# 02.net
KiCad netlist of a schematic drawn in Altium Designer
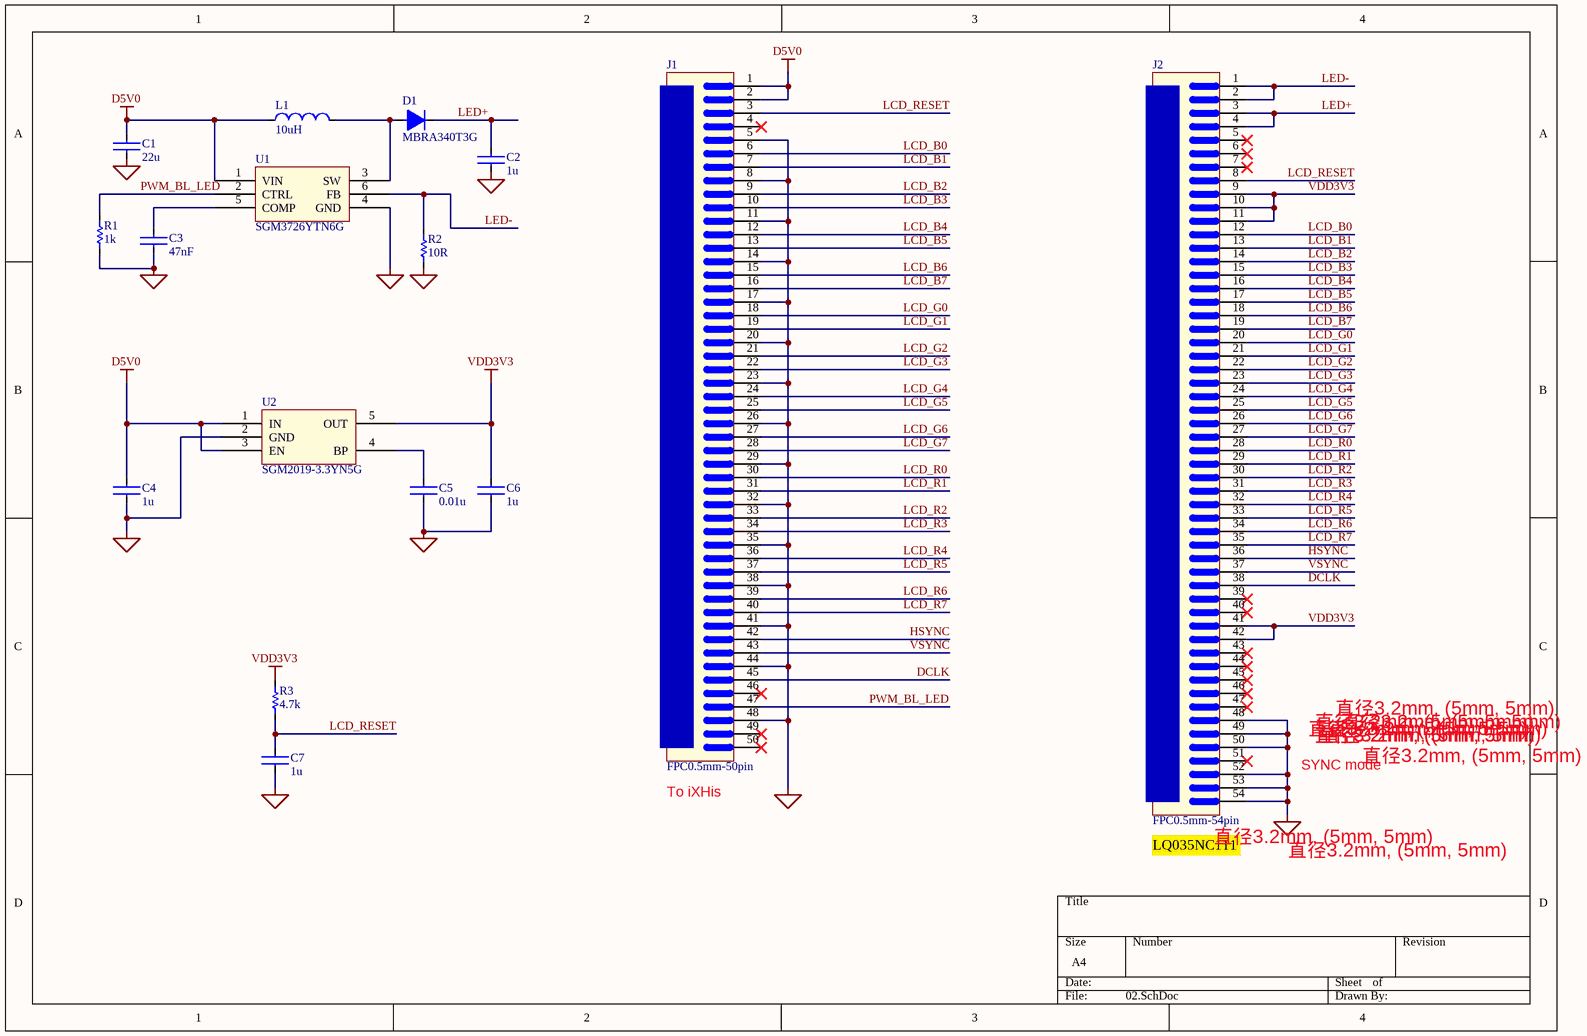
[diagram p0: 02.SchDoc]

(export (version "E")
  (design (tool "Eeschema 10.0.6"))
  (components
    (comp (ref "C1")
      (value "22u")
      (footprint "CAPC1608X09N_C0603")
      (description "CAP,Ceramic,X7R,10%,6.3V,22uF,0603")
      (libsource (lib "C0603") (part "CAP114"))
    )
    (comp (ref "C2")
      (value "1u")
      (footprint "CAPC2012X14N_C0805")
      (description "CAP,Ceramic,X7R,10%,25V,1uF,0805")
      (libsource (lib "C0805") (part "CAP110"))
    )
    (comp (ref "C3")
      (value "47nF")
      (footprint "CAPC1608X09N_C0603")
      (description "CAP,Ceramic,X7R,10%,50V,47nF,0603")
      (libsource (lib "C0603") (part "CAP115"))
    )
    (comp (ref "C4")
      (value "1u")
      (footprint "CAPC1608X09N_C0603")
      (description "CAP,Ceramic,X7R,10%,16V,1uF,0603")
      (libsource (lib "C0603") (part "CAP12"))
    )
    (comp (ref "C5")
      (value "0.01u")
      (footprint "CAPC1608X09N_C0603")
      (description "CAP,Ceramic,X7R,10%,50V,0.01uF,0603")
      (libsource (lib "C0603") (part "CAP112"))
    )
    (comp (ref "C6")
      (value "1u")
      (footprint "CAPC1608X09N_C0603")
      (description "CAP,Ceramic,X7R,10%,16V,1uF,0603")
      (libsource (lib "AD15_libpkg") (part "CAP12"))
    )
    (comp (ref "C7")
      (value "1u")
      (footprint "CAPC1608X09N_C0603")
      (description "CAP,Ceramic,X7R,10%,16V,1uF,0603")
      (libsource (lib "C0603") (part "CAP12"))
    )
    (comp (ref "D1")
      (value "MBRA340T3G")
      (footprint "DIOM4326X23N_SMA")
      (description "Schottky Barrier Rectifier,40V,3A,SMA")
      (libsource (lib "AD15_schlib") (part "MBRA340T3G"))
    )
    (comp (ref "J1")
      (value "FPC0.5mm-50pin")
      (footprint "FPC0.5mm-50pin")
      (description "FFC socket,50-Pin,top contact,0.5mm Pitch,SMD")
      (libsource (lib "AD15_schlib") (part "FPC0.5mm_04"))
    )
    (comp (ref "J2")
      (value "FPC0.5mm-54pin")
      (footprint "FPC0.5mm-54pin")
      (description "FFC socket,54-Pin,bottom contact,0.5mm Pitch,SMD")
      (libsource (lib "AD15_schlib") (part "FPC0.5mm_03"))
    )
    (comp (ref "L1")
      (value "10uH")
      (footprint "NRS3015T100MNGH")
      (description "Inductor,10uH,700mA,0.22ohm,SMD")
      (libsource (lib "AD15_schlib") (part "NRS3015T100MNGH"))
    )
    (comp (ref "R1")
      (value "1k")
      (footprint "RESC1608X05N_R0603")
      (description "RES,1k,1%,1/10W,0603")
      (libsource (lib "R0603") (part "RES11"))
    )
    (comp (ref "R2")
      (value "10R")
      (footprint "R0805")
      (description "RES,10R,1%,1/8W,0805")
      (libsource (lib "AD15_schlib") (part "RES113_2"))
    )
    (comp (ref "R3")
      (value "4.7k")
      (footprint "RESC1608X05N_R0603")
      (description "RES,4.7k,1%,1/10W,0603")
      (libsource (lib "R0603") (part "RES15"))
    )
    (comp (ref "U1")
      (value "SGM3726YTN6G")
      (footprint "TSOT23-6_SGM3726")
      (description "IC, boost converter, 1.1A, TSOT23-6")
      (libsource (lib "AD15_SGM_schlib") (part "SGM3726YTN6G"))
    )
    (comp (ref "U2")
      (value "SGM2019-3.3YN5G")
      (footprint "SOT95P280X125-5N_SGM2019")
      (description "IC,LDO 3.3V@300mA,SOT23-5")
      (libsource (lib "AD15_SGM_schlib") (part "SGM2019-3.3"))
    )
  )
  (nets
    (net (code "1") (name "/DCLK") (class "Default")
      (node (ref "J1") (pin "45") (pinfunction "45_45") (pintype "passive"))
      (node (ref "J2") (pin "38") (pinfunction "38_38") (pintype "passive"))
    )
    (net (code "2") (name "/HSYNC") (class "Default")
      (node (ref "J1") (pin "42") (pinfunction "42_42") (pintype "passive"))
      (node (ref "J2") (pin "36") (pinfunction "36_36") (pintype "passive"))
    )
    (net (code "3") (name "/LCD_B0") (class "Default")
      (node (ref "J1") (pin "6") (pinfunction "5_6") (pintype "passive"))
      (node (ref "J2") (pin "12") (pinfunction "12_12") (pintype "passive"))
    )
    (net (code "4") (name "/LCD_B1") (class "Default")
      (node (ref "J1") (pin "7") (pinfunction "6_7") (pintype "passive"))
      (node (ref "J2") (pin "13") (pinfunction "13_13") (pintype "passive"))
    )
    (net (code "5") (name "/LCD_B2") (class "Default")
      (node (ref "J1") (pin "9") (pinfunction "8_9") (pintype "passive"))
      (node (ref "J2") (pin "14") (pinfunction "14_14") (pintype "passive"))
    )
    (net (code "6") (name "/LCD_B3") (class "Default")
      (node (ref "J1") (pin "10") (pinfunction "9_10") (pintype "passive"))
      (node (ref "J2") (pin "15") (pinfunction "15_15") (pintype "passive"))
    )
    (net (code "7") (name "/LCD_B4") (class "Default")
      (node (ref "J1") (pin "12") (pinfunction "12_12") (pintype "passive"))
      (node (ref "J2") (pin "16") (pinfunction "16_16") (pintype "passive"))
    )
    (net (code "8") (name "/LCD_B5") (class "Default")
      (node (ref "J1") (pin "13") (pinfunction "13_13") (pintype "passive"))
      (node (ref "J2") (pin "17") (pinfunction "17_17") (pintype "passive"))
    )
    (net (code "9") (name "/LCD_B6") (class "Default")
      (node (ref "J1") (pin "15") (pinfunction "15_15") (pintype "passive"))
      (node (ref "J2") (pin "18") (pinfunction "18_18") (pintype "passive"))
    )
    (net (code "10") (name "/LCD_B7") (class "Default")
      (node (ref "J1") (pin "16") (pinfunction "16_16") (pintype "passive"))
      (node (ref "J2") (pin "19") (pinfunction "19_19") (pintype "passive"))
    )
    (net (code "11") (name "/LCD_G0") (class "Default")
      (node (ref "J1") (pin "18") (pinfunction "18_18") (pintype "passive"))
      (node (ref "J2") (pin "20") (pinfunction "20_20") (pintype "passive"))
    )
    (net (code "12") (name "/LCD_G1") (class "Default")
      (node (ref "J1") (pin "19") (pinfunction "19_19") (pintype "passive"))
      (node (ref "J2") (pin "21") (pinfunction "21_21") (pintype "passive"))
    )
    (net (code "13") (name "/LCD_G2") (class "Default")
      (node (ref "J1") (pin "21") (pinfunction "21_21") (pintype "passive"))
      (node (ref "J2") (pin "22") (pinfunction "22_22") (pintype "passive"))
    )
    (net (code "14") (name "/LCD_G3") (class "Default")
      (node (ref "J1") (pin "22") (pinfunction "22_22") (pintype "passive"))
      (node (ref "J2") (pin "23") (pinfunction "23_23") (pintype "passive"))
    )
    (net (code "15") (name "/LCD_G4") (class "Default")
      (node (ref "J1") (pin "24") (pinfunction "24_24") (pintype "passive"))
      (node (ref "J2") (pin "24") (pinfunction "24_24") (pintype "passive"))
    )
    (net (code "16") (name "/LCD_G5") (class "Default")
      (node (ref "J1") (pin "25") (pinfunction "25_25") (pintype "passive"))
      (node (ref "J2") (pin "25") (pinfunction "25_25") (pintype "passive"))
    )
    (net (code "17") (name "/LCD_G6") (class "Default")
      (node (ref "J1") (pin "27") (pinfunction "27_27") (pintype "passive"))
      (node (ref "J2") (pin "26") (pinfunction "26_26") (pintype "passive"))
    )
    (net (code "18") (name "/LCD_G7") (class "Default")
      (node (ref "J1") (pin "28") (pinfunction "28_28") (pintype "passive"))
      (node (ref "J2") (pin "27") (pinfunction "27_27") (pintype "passive"))
    )
    (net (code "19") (name "/LCD_R0") (class "Default")
      (node (ref "J1") (pin "30") (pinfunction "30_30") (pintype "passive"))
      (node (ref "J2") (pin "28") (pinfunction "28_28") (pintype "passive"))
    )
    (net (code "20") (name "/LCD_R1") (class "Default")
      (node (ref "J1") (pin "31") (pinfunction "31_31") (pintype "passive"))
      (node (ref "J2") (pin "29") (pinfunction "29_29") (pintype "passive"))
    )
    (net (code "21") (name "/LCD_R2") (class "Default")
      (node (ref "J1") (pin "33") (pinfunction "33_33") (pintype "passive"))
      (node (ref "J2") (pin "30") (pinfunction "30_30") (pintype "passive"))
    )
    (net (code "22") (name "/LCD_R3") (class "Default")
      (node (ref "J1") (pin "34") (pinfunction "34_34") (pintype "passive"))
      (node (ref "J2") (pin "31") (pinfunction "31_31") (pintype "passive"))
    )
    (net (code "23") (name "/LCD_R4") (class "Default")
      (node (ref "J1") (pin "36") (pinfunction "36_36") (pintype "passive"))
      (node (ref "J2") (pin "32") (pinfunction "32_32") (pintype "passive"))
    )
    (net (code "24") (name "/LCD_R5") (class "Default")
      (node (ref "J1") (pin "37") (pinfunction "37_37") (pintype "passive"))
      (node (ref "J2") (pin "33") (pinfunction "33_33") (pintype "passive"))
    )
    (net (code "25") (name "/LCD_R6") (class "Default")
      (node (ref "J1") (pin "39") (pinfunction "39_39") (pintype "passive"))
      (node (ref "J2") (pin "34") (pinfunction "34_34") (pintype "passive"))
    )
    (net (code "26") (name "/LCD_R7") (class "Default")
      (node (ref "J1") (pin "40") (pinfunction "40_40") (pintype "passive"))
      (node (ref "J2") (pin "35") (pinfunction "35_35") (pintype "passive"))
    )
    (net (code "27") (name "/LCD_RESET") (class "Default")
      (node (ref "C7") (pin "1") (pinfunction "0_1") (pintype "passive"))
      (node (ref "J1") (pin "3") (pinfunction "2_3") (pintype "passive"))
      (node (ref "J2") (pin "8") (pinfunction "7_8") (pintype "passive"))
      (node (ref "R3") (pin "1") (pinfunction "0_1") (pintype "passive"))
    )
    (net (code "28") (name "/LED+") (class "Default")
      (node (ref "C2") (pin "1") (pinfunction "0_1") (pintype "passive"))
      (node (ref "D1") (pin "2") (pinfunction "K_2") (pintype "passive"))
      (node (ref "J2") (pin "3") (pinfunction "2_3") (pintype "passive"))
      (node (ref "J2") (pin "4") (pinfunction "3_4") (pintype "passive"))
    )
    (net (code "29") (name "/LED-") (class "Default")
      (node (ref "J2") (pin "1") (pinfunction "0_1") (pintype "passive"))
      (node (ref "J2") (pin "2") (pinfunction "1_2") (pintype "passive"))
      (node (ref "R2") (pin "2") (pinfunction "2_2") (pintype "passive"))
      (node (ref "U1") (pin "6") (pinfunction "FB_6") (pintype "passive"))
    )
    (net (code "30") (name "/PWM_BL_LED") (class "Default")
      (node (ref "J1") (pin "47") (pinfunction "47_47") (pintype "passive"))
      (node (ref "R1") (pin "2") (pinfunction "2_2") (pintype "passive"))
      (node (ref "U1") (pin "2") (pinfunction "CTRL_2") (pintype "passive"))
    )
    (net (code "31") (name "/VSYNC") (class "Default")
      (node (ref "J1") (pin "43") (pinfunction "43_43") (pintype "passive"))
      (node (ref "J2") (pin "37") (pinfunction "37_37") (pintype "passive"))
    )
    (net (code "32") (name "D5V0") (class "Default")
      (node (ref "C1") (pin "1") (pinfunction "0_1") (pintype "passive"))
      (node (ref "C4") (pin "1") (pinfunction "0_1") (pintype "passive"))
      (node (ref "J1") (pin "1") (pinfunction "0_1") (pintype "passive"))
      (node (ref "J1") (pin "2") (pinfunction "1_2") (pintype "passive"))
      (node (ref "L1") (pin "2") (pinfunction "1_2") (pintype "passive"))
      (node (ref "U1") (pin "1") (pinfunction "VIN_1") (pintype "passive"))
      (node (ref "U2") (pin "1") (pinfunction "IN_1") (pintype "passive"))
      (node (ref "U2") (pin "3") (pinfunction "EN_3") (pintype "passive"))
    )
    (net (code "33") (name "GND") (class "Default")
      (node (ref "C1") (pin "2") (pinfunction "1_2") (pintype "passive"))
      (node (ref "C2") (pin "2") (pinfunction "1_2") (pintype "passive"))
      (node (ref "C3") (pin "2") (pinfunction "1_2") (pintype "passive"))
      (node (ref "C4") (pin "2") (pinfunction "1_2") (pintype "passive"))
      (node (ref "C5") (pin "2") (pinfunction "1_2") (pintype "passive"))
      (node (ref "C6") (pin "2") (pinfunction "1_2") (pintype "passive"))
      (node (ref "C7") (pin "2") (pinfunction "1_2") (pintype "passive"))
      (node (ref "J1") (pin "11") (pinfunction "11_11") (pintype "passive"))
      (node (ref "J1") (pin "14") (pinfunction "14_14") (pintype "passive"))
      (node (ref "J1") (pin "17") (pinfunction "17_17") (pintype "passive"))
      (node (ref "J1") (pin "20") (pinfunction "20_20") (pintype "passive"))
      (node (ref "J1") (pin "23") (pinfunction "23_23") (pintype "passive"))
      (node (ref "J1") (pin "26") (pinfunction "26_26") (pintype "passive"))
      (node (ref "J1") (pin "29") (pinfunction "29_29") (pintype "passive"))
      (node (ref "J1") (pin "32") (pinfunction "32_32") (pintype "passive"))
      (node (ref "J1") (pin "35") (pinfunction "35_35") (pintype "passive"))
      (node (ref "J1") (pin "38") (pinfunction "38_38") (pintype "passive"))
      (node (ref "J1") (pin "41") (pinfunction "41_41") (pintype "passive"))
      (node (ref "J1") (pin "44") (pinfunction "44_44") (pintype "passive"))
      (node (ref "J1") (pin "48") (pinfunction "48_48") (pintype "passive"))
      (node (ref "J1") (pin "5") (pinfunction "4_5") (pintype "passive"))
      (node (ref "J1") (pin "8") (pinfunction "7_8") (pintype "passive"))
      (node (ref "J2") (pin "48") (pinfunction "48_48") (pintype "passive"))
      (node (ref "J2") (pin "49") (pinfunction "49_49") (pintype "passive"))
      (node (ref "J2") (pin "50") (pinfunction "50_50") (pintype "passive"))
      (node (ref "J2") (pin "52") (pinfunction "52_52") (pintype "passive"))
      (node (ref "J2") (pin "53") (pinfunction "53_53") (pintype "passive"))
      (node (ref "J2") (pin "54") (pinfunction "54_54") (pintype "passive"))
      (node (ref "R1") (pin "1") (pinfunction "0_1") (pintype "passive"))
      (node (ref "R2") (pin "1") (pinfunction "0_1") (pintype "passive"))
      (node (ref "U1") (pin "4") (pinfunction "GND_4") (pintype "passive"))
      (node (ref "U2") (pin "2") (pinfunction "GND_2") (pintype "passive"))
    )
    (net (code "34") (name "Net-(C3-0)") (class "Default")
      (node (ref "C3") (pin "1") (pinfunction "0_1") (pintype "passive"))
      (node (ref "U1") (pin "5") (pinfunction "COMP_5") (pintype "passive"))
    )
    (net (code "35") (name "Net-(C5-0)") (class "Default")
      (node (ref "C5") (pin "1") (pinfunction "0_1") (pintype "passive"))
      (node (ref "U2") (pin "4") (pinfunction "BP_4") (pintype "passive"))
    )
    (net (code "36") (name "Net-(D1-A)") (class "Default")
      (node (ref "D1") (pin "1") (pinfunction "A_1") (pintype "passive"))
      (node (ref "L1") (pin "1") (pinfunction "0_1") (pintype "passive"))
      (node (ref "U1") (pin "3") (pinfunction "SW_3") (pintype "passive"))
    )
    (net (code "37") (name "VDD3V3") (class "Default")
      (node (ref "C6") (pin "1") (pinfunction "0_1") (pintype "passive"))
      (node (ref "J2") (pin "10") (pinfunction "9_10") (pintype "passive"))
      (node (ref "J2") (pin "11") (pinfunction "11_11") (pintype "passive"))
      (node (ref "J2") (pin "41") (pinfunction "41_41") (pintype "passive"))
      (node (ref "J2") (pin "42") (pinfunction "42_42") (pintype "passive"))
      (node (ref "J2") (pin "9") (pinfunction "8_9") (pintype "passive"))
      (node (ref "R3") (pin "2") (pinfunction "2_2") (pintype "passive"))
      (node (ref "U2") (pin "5") (pinfunction "OUT_5") (pintype "passive"))
    )
    (net (code "38") (name "unconnected-(J1-3-Pad4)") (class "Default")
      (node (ref "J1") (pin "4") (pinfunction "3_4") (pintype "passive+no_connect"))
    )
    (net (code "39") (name "unconnected-(J1-Pad46)") (class "Default")
      (node (ref "J1") (pin "46") (pinfunction "46_46") (pintype "passive+no_connect"))
    )
    (net (code "40") (name "unconnected-(J1-Pad49)") (class "Default")
      (node (ref "J1") (pin "49") (pinfunction "49_49") (pintype "passive+no_connect"))
    )
    (net (code "41") (name "unconnected-(J1-Pad50)") (class "Default")
      (node (ref "J1") (pin "50") (pinfunction "50_50") (pintype "passive+no_connect"))
    )
    (net (code "42") (name "unconnected-(J2-4-Pad5)") (class "Default")
      (node (ref "J2") (pin "5") (pinfunction "4_5") (pintype "passive+no_connect"))
    )
    (net (code "43") (name "unconnected-(J2-5-Pad6)") (class "Default")
      (node (ref "J2") (pin "6") (pinfunction "5_6") (pintype "passive+no_connect"))
    )
    (net (code "44") (name "unconnected-(J2-6-Pad7)") (class "Default")
      (node (ref "J2") (pin "7") (pinfunction "6_7") (pintype "passive+no_connect"))
    )
    (net (code "45") (name "unconnected-(J2-Pad39)") (class "Default")
      (node (ref "J2") (pin "39") (pinfunction "39_39") (pintype "passive+no_connect"))
    )
    (net (code "46") (name "unconnected-(J2-Pad40)") (class "Default")
      (node (ref "J2") (pin "40") (pinfunction "40_40") (pintype "passive+no_connect"))
    )
    (net (code "47") (name "unconnected-(J2-Pad43)") (class "Default")
      (node (ref "J2") (pin "43") (pinfunction "43_43") (pintype "passive+no_connect"))
    )
    (net (code "48") (name "unconnected-(J2-Pad44)") (class "Default")
      (node (ref "J2") (pin "44") (pinfunction "44_44") (pintype "passive+no_connect"))
    )
    (net (code "49") (name "unconnected-(J2-Pad45)") (class "Default")
      (node (ref "J2") (pin "45") (pinfunction "45_45") (pintype "passive+no_connect"))
    )
    (net (code "50") (name "unconnected-(J2-Pad46)") (class "Default")
      (node (ref "J2") (pin "46") (pinfunction "46_46") (pintype "passive+no_connect"))
    )
    (net (code "51") (name "unconnected-(J2-Pad47)") (class "Default")
      (node (ref "J2") (pin "47") (pinfunction "47_47") (pintype "passive+no_connect"))
    )
    (net (code "52") (name "unconnected-(J2-Pad51)") (class "Default")
      (node (ref "J2") (pin "51") (pinfunction "51_51") (pintype "passive+no_connect"))
    )
  )
)
